# SCH_Arduino-Tx_2024-08-14.net
KiCad netlist of a schematic drawn in EasyEDA
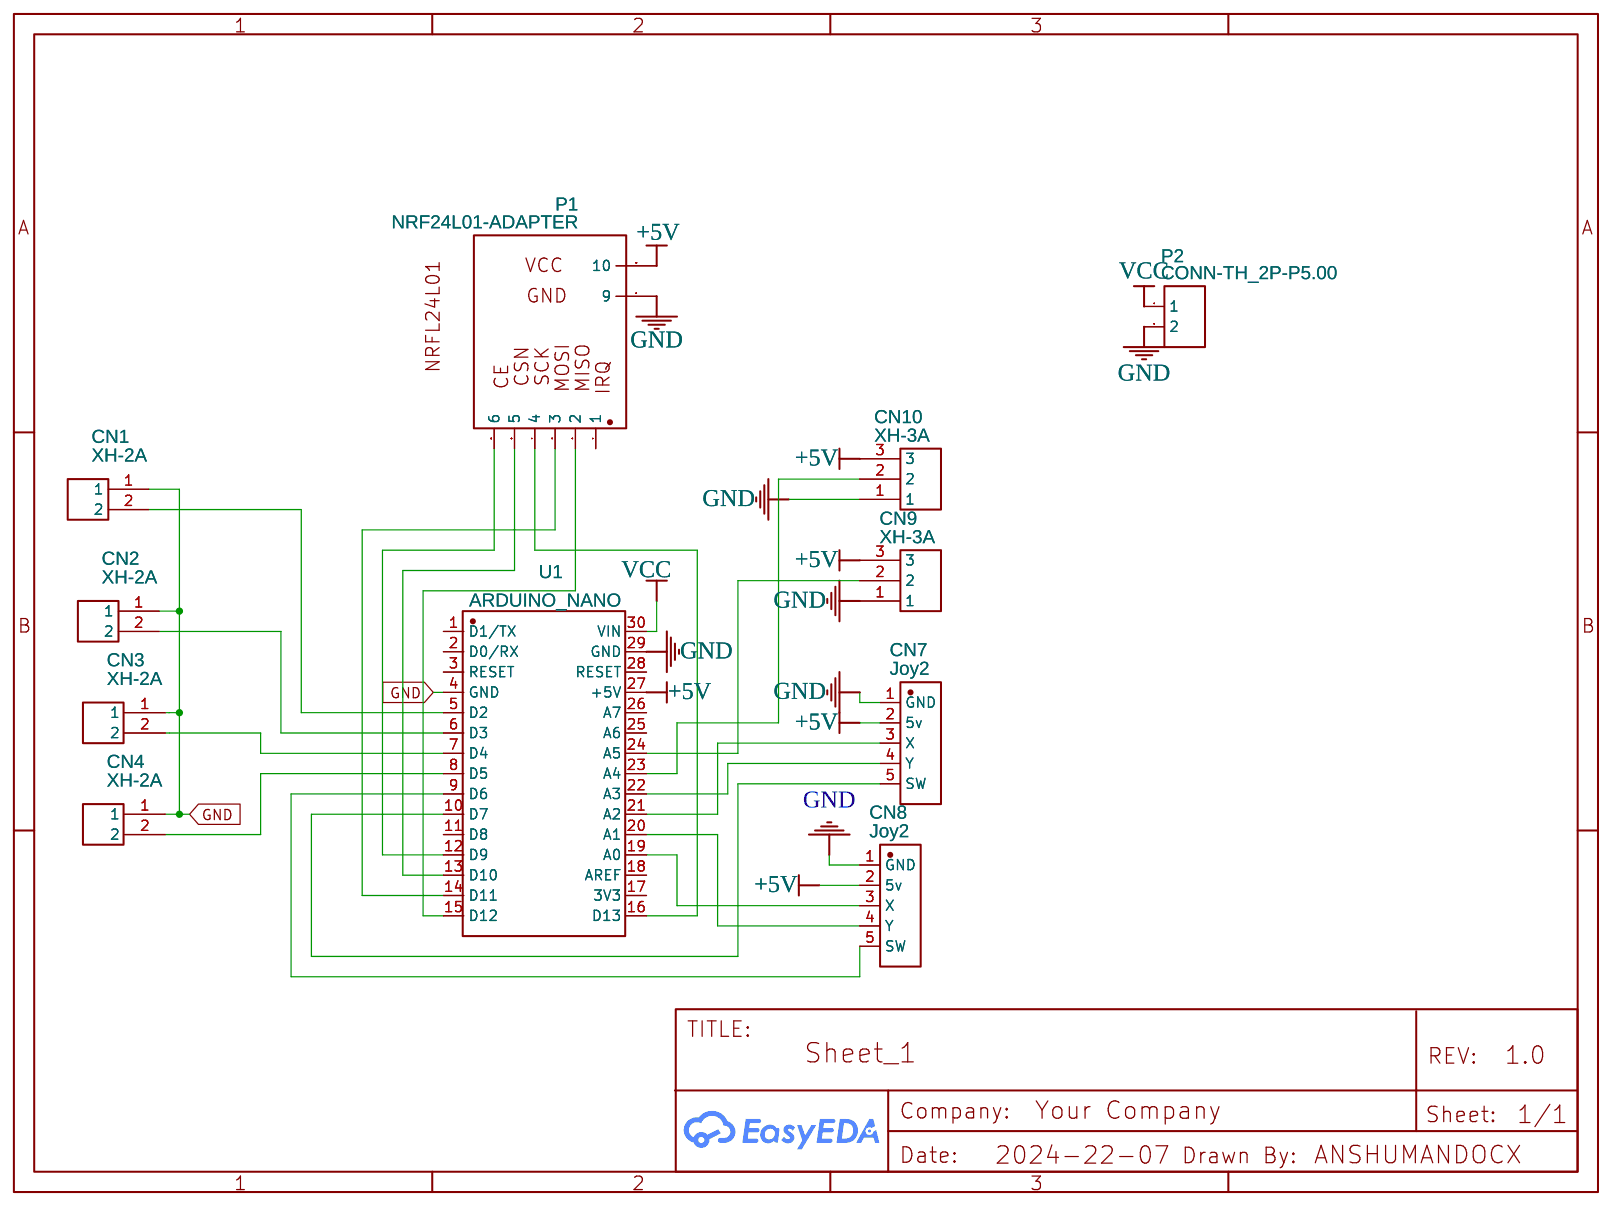
[diagram p0: schematic sheet]

(export (version "E")
  (design (tool "Eeschema 10.0.6"))
  (components
    (comp (ref "CN1")
      (value "XH-2A")
      (fields (field (name "Manufacturer") "BOOMELE(博穆精密)"))
      (libsource (lib "") (part "XH-2A_1"))
    )
    (comp (ref "CN2")
      (value "XH-2A")
      (fields (field (name "Manufacturer") "BOOMELE(博穆精密)"))
      (libsource (lib "") (part "XH-2A_1"))
    )
    (comp (ref "CN3")
      (value "XH-2A")
      (fields (field (name "Manufacturer") "BOOMELE(博穆精密)"))
      (libsource (lib "") (part "XH-2A"))
    )
    (comp (ref "CN4")
      (value "XH-2A")
      (fields (field (name "Manufacturer") "BOOMELE(博穆精密)"))
      (libsource (lib "") (part "XH-2A"))
    )
    (comp (ref "CN7")
      (value "Joy2")
      (fields (field (name "Manufacturer Part") "XH-5A") (field (name "Manufacturer") "BOOMELE(博穆精密)"))
      (libsource (lib "") (part "XH-5A"))
    )
    (comp (ref "CN8")
      (value "Joy2")
      (fields (field (name "Manufacturer Part") "XH-5A") (field (name "Manufacturer") "BOOMELE(博穆精密)"))
      (libsource (lib "") (part "XH-5A"))
    )
    (comp (ref "CN9")
      (value "XH-3A")
      (fields (field (name "Manufacturer") "BOOMELE(博穆精密)"))
      (libsource (lib "") (part "XH-3A"))
    )
    (comp (ref "CN10")
      (value "XH-3A")
      (fields (field (name "Manufacturer") "BOOMELE(博穆精密)"))
      (libsource (lib "") (part "XH-3A"))
    )
    (comp (ref "P1")
      (value "NRF24L01-ADAPTER")
      (fields (field (name "Manufacturer Part") "WJ2EDGVC-5.08-06P") (field (name "Manufacturer") "ReliaPro"))
      (libsource (lib "") (part "NRF24L01-ADAPTER"))
    )
    (comp (ref "P2") (value "CONN-TH_2P-P5.00") (libsource (lib "") (part "CONN-TH_2P-P5.00")))
    (comp (ref "U1") (value "ARDUINO_NANO") (libsource (lib "") (part "ARDUINO_NANO")))
  )
  (nets
    (net (code "1") (name "+5V") (class "Default")
      (node (ref "CN10") (pin "3") (pinfunction "3_3") (pintype "unspecified"))
      (node (ref "CN7") (pin "2") (pinfunction "5v_2") (pintype "unspecified"))
      (node (ref "CN8") (pin "2") (pinfunction "5v_2") (pintype "unspecified"))
      (node (ref "CN9") (pin "3") (pinfunction "3_3") (pintype "unspecified"))
      (node (ref "P1") (pin "10") (pinfunction "10_10") (pintype "unspecified"))
      (node (ref "U1") (pin "27") (pinfunction "+5V_27") (pintype "unspecified"))
    )
    (net (code "2") (name "GND") (class "Default")
      (node (ref "CN1") (pin "1") (pinfunction "1_1") (pintype "unspecified"))
      (node (ref "CN10") (pin "1") (pinfunction "1_1") (pintype "unspecified"))
      (node (ref "CN2") (pin "1") (pinfunction "1_1") (pintype "unspecified"))
      (node (ref "CN3") (pin "1") (pinfunction "1_1") (pintype "unspecified"))
      (node (ref "CN4") (pin "1") (pinfunction "1_1") (pintype "unspecified"))
      (node (ref "CN7") (pin "1") (pinfunction "GND_1") (pintype "unspecified"))
      (node (ref "CN8") (pin "1") (pinfunction "GND_1") (pintype "unspecified"))
      (node (ref "CN9") (pin "1") (pinfunction "1_1") (pintype "unspecified"))
      (node (ref "P1") (pin "9") (pinfunction "9_9") (pintype "unspecified"))
      (node (ref "P2") (pin "2") (pinfunction "2_2") (pintype "unspecified"))
      (node (ref "U1") (pin "29") (pinfunction "GND_29") (pintype "unspecified"))
      (node (ref "U1") (pin "4") (pinfunction "GND_4") (pintype "unspecified"))
    )
    (net (code "3") (name "Net-(CN7-SW)") (class "Default")
      (node (ref "CN7") (pin "5") (pinfunction "SW_5") (pintype "unspecified"))
      (node (ref "U1") (pin "10") (pinfunction "D7_10") (pintype "unspecified"))
    )
    (net (code "4") (name "Net-(CN7-X)") (class "Default")
      (node (ref "CN7") (pin "3") (pinfunction "X_3") (pintype "unspecified"))
      (node (ref "U1") (pin "21") (pinfunction "A2_21") (pintype "unspecified"))
    )
    (net (code "5") (name "Net-(CN7-Y)") (class "Default")
      (node (ref "CN7") (pin "4") (pinfunction "Y_4") (pintype "unspecified"))
      (node (ref "U1") (pin "22") (pinfunction "A3_22") (pintype "unspecified"))
    )
    (net (code "6") (name "Net-(CN8-SW)") (class "Default")
      (node (ref "CN8") (pin "5") (pinfunction "SW_5") (pintype "unspecified"))
      (node (ref "U1") (pin "9") (pinfunction "D6_9") (pintype "unspecified"))
    )
    (net (code "7") (name "Net-(CN8-X)") (class "Default")
      (node (ref "CN8") (pin "3") (pinfunction "X_3") (pintype "unspecified"))
      (node (ref "U1") (pin "19") (pinfunction "A0_19") (pintype "unspecified"))
    )
    (net (code "8") (name "Net-(CN8-Y)") (class "Default")
      (node (ref "CN8") (pin "4") (pinfunction "Y_4") (pintype "unspecified"))
      (node (ref "U1") (pin "20") (pinfunction "A1_20") (pintype "unspecified"))
    )
    (net (code "9") (name "Net-(U1-A4)") (class "Default")
      (node (ref "CN10") (pin "2") (pinfunction "2_2") (pintype "unspecified"))
      (node (ref "U1") (pin "23") (pinfunction "A4_23") (pintype "unspecified"))
    )
    (net (code "10") (name "Net-(U1-A5)") (class "Default")
      (node (ref "CN9") (pin "2") (pinfunction "2_2") (pintype "unspecified"))
      (node (ref "U1") (pin "24") (pinfunction "A5_24") (pintype "unspecified"))
    )
    (net (code "11") (name "Net-(U1-D2)") (class "Default")
      (node (ref "CN1") (pin "2") (pinfunction "2_2") (pintype "unspecified"))
      (node (ref "U1") (pin "5") (pinfunction "D2_5") (pintype "unspecified"))
    )
    (net (code "12") (name "Net-(U1-D3)") (class "Default")
      (node (ref "CN2") (pin "2") (pinfunction "2_2") (pintype "unspecified"))
      (node (ref "U1") (pin "6") (pinfunction "D3_6") (pintype "unspecified"))
    )
    (net (code "13") (name "Net-(U1-D4)") (class "Default")
      (node (ref "CN3") (pin "2") (pinfunction "2_2") (pintype "unspecified"))
      (node (ref "U1") (pin "7") (pinfunction "D4_7") (pintype "unspecified"))
    )
    (net (code "14") (name "Net-(U1-D5)") (class "Default")
      (node (ref "CN4") (pin "2") (pinfunction "2_2") (pintype "unspecified"))
      (node (ref "U1") (pin "8") (pinfunction "D5_8") (pintype "unspecified"))
    )
    (net (code "15") (name "Net-(U1-D9)") (class "Default")
      (node (ref "P1") (pin "6") (pinfunction "6_6") (pintype "unspecified"))
      (node (ref "U1") (pin "12") (pinfunction "D9_12") (pintype "unspecified"))
    )
    (net (code "16") (name "Net-(U1-D10)") (class "Default")
      (node (ref "P1") (pin "5") (pinfunction "5_5") (pintype "unspecified"))
      (node (ref "U1") (pin "13") (pinfunction "D10_13") (pintype "unspecified"))
    )
    (net (code "17") (name "Net-(U1-D11)") (class "Default")
      (node (ref "P1") (pin "3") (pinfunction "3_3") (pintype "unspecified"))
      (node (ref "U1") (pin "14") (pinfunction "D11_14") (pintype "unspecified"))
    )
    (net (code "18") (name "Net-(U1-D12)") (class "Default")
      (node (ref "P1") (pin "2") (pinfunction "2_2") (pintype "unspecified"))
      (node (ref "U1") (pin "15") (pinfunction "D12_15") (pintype "unspecified"))
    )
    (net (code "19") (name "Net-(U1-D13)") (class "Default")
      (node (ref "P1") (pin "4") (pinfunction "4_4") (pintype "unspecified"))
      (node (ref "U1") (pin "16") (pinfunction "D13_16") (pintype "unspecified"))
    )
    (net (code "20") (name "VCC") (class "Default")
      (node (ref "P2") (pin "1") (pinfunction "1_1") (pintype "unspecified"))
      (node (ref "U1") (pin "30") (pinfunction "VIN_30") (pintype "unspecified"))
    )
    (net (code "21") (name "unconnected-(P1-Pad1)") (class "Default")
      (node (ref "P1") (pin "1") (pinfunction "1_1") (pintype "unspecified"))
    )
    (net (code "22") (name "unconnected-(U1-3V3-Pad17)") (class "Default")
      (node (ref "U1") (pin "17") (pinfunction "3V3_17") (pintype "unspecified"))
    )
    (net (code "23") (name "unconnected-(U1-A6-Pad25)") (class "Default")
      (node (ref "U1") (pin "25") (pinfunction "A6_25") (pintype "unspecified"))
    )
    (net (code "24") (name "unconnected-(U1-A7-Pad26)") (class "Default")
      (node (ref "U1") (pin "26") (pinfunction "A7_26") (pintype "unspecified"))
    )
    (net (code "25") (name "unconnected-(U1-AREF-Pad18)") (class "Default")
      (node (ref "U1") (pin "18") (pinfunction "AREF_18") (pintype "unspecified"))
    )
    (net (code "26") (name "unconnected-(U1-D0{slash}RX-Pad2)") (class "Default")
      (node (ref "U1") (pin "2") (pinfunction "D0/RX_2") (pintype "unspecified"))
    )
    (net (code "27") (name "unconnected-(U1-D1{slash}TX-Pad1)") (class "Default")
      (node (ref "U1") (pin "1") (pinfunction "D1/TX_1") (pintype "unspecified"))
    )
    (net (code "28") (name "unconnected-(U1-D8-Pad11)") (class "Default")
      (node (ref "U1") (pin "11") (pinfunction "D8_11") (pintype "unspecified"))
    )
    (net (code "29") (name "unconnected-(U1-RESET-Pad3)") (class "Default")
      (node (ref "U1") (pin "3") (pinfunction "RESET_3") (pintype "unspecified"))
    )
    (net (code "30") (name "unconnected-(U1-RESET-Pad28)") (class "Default")
      (node (ref "U1") (pin "28") (pinfunction "RESET_28") (pintype "unspecified"))
    )
  )
)
